# other.net
KiCad netlist of a schematic drawn in Altium Designer
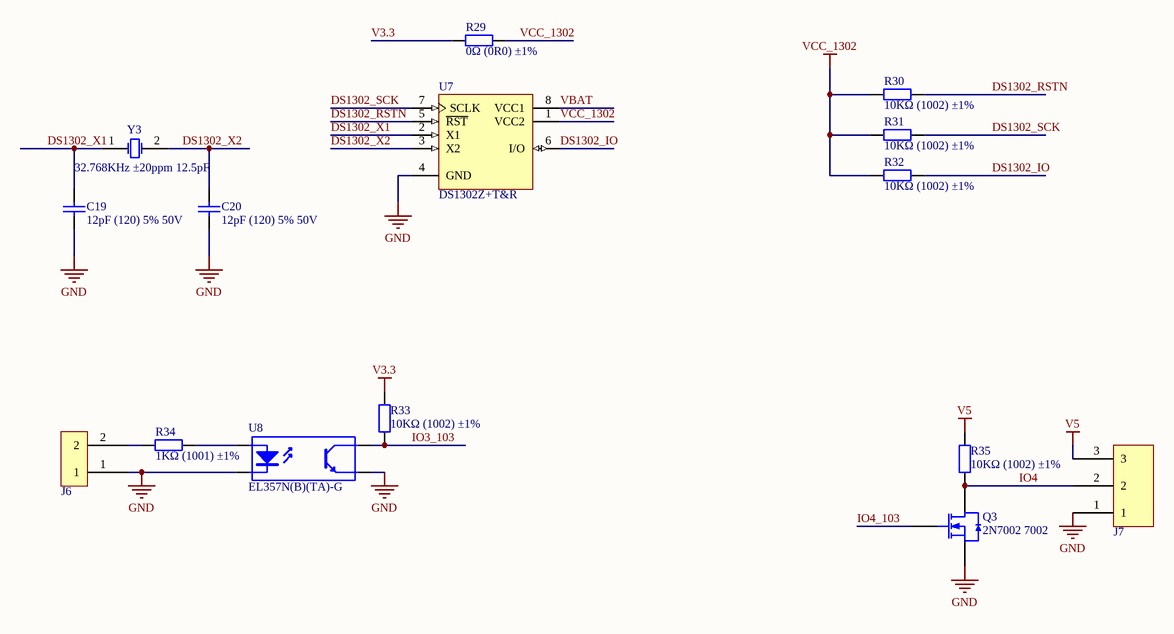
[diagram p0: other.SchDoc]

(export (version "E")
  (design (tool "Eeschema 10.0.6"))
  (components
    (comp (ref "C19")
      (value "12pF (120) 5% 50V")
      (footprint "0603_C")
      (description "贴片电容")
      (libsource (lib "Miscellaneous Devices LC") (part "0603 12pF (120) 5% 50V"))
    )
    (comp (ref "C20")
      (value "12pF (120) 5% 50V")
      (footprint "0603_C")
      (description "贴片电容")
      (libsource (lib "Miscellaneous Devices LC") (part "0603 12pF (120) 5% 50V"))
    )
    (comp (ref "J6") (value "KF301-2P") (footprint "KF301-2P") (libsource (lib "CHK-I") (part "KF301-2P")))
    (comp (ref "J7") (value "KF301-3P") (footprint "KF301-3P") (libsource (lib "CHK-I") (part "KF301-3P")))
    (comp (ref "Q3")
      (value "2N7002 7002")
      (footprint "SOT-23(SOT-23-3)")
      (description "MOS(场效应管)")
      (libsource (lib "Miscellaneous Devices LC") (part "2N7002 7002"))
    )
    (comp (ref "R29")
      (value "0Ω (0R0) ±1%")
      (footprint "1206_R")
      (description "贴片电阻")
      (libsource (lib "Miscellaneous Devices LC") (part "1206 0Ω (0R0) 1%"))
    )
    (comp (ref "R30")
      (value "10KΩ (1002) ±1%")
      (footprint "0603_R")
      (description "贴片电阻")
      (libsource (lib "Miscellaneous Devices LC") (part "0603 10KΩ (1002) 1%"))
    )
    (comp (ref "R31")
      (value "10KΩ (1002) ±1%")
      (footprint "0603_R")
      (description "贴片电阻")
      (libsource (lib "Miscellaneous Devices LC") (part "0603 10KΩ (1002) 1%"))
    )
    (comp (ref "R32")
      (value "10KΩ (1002) ±1%")
      (footprint "0603_R")
      (description "贴片电阻")
      (libsource (lib "Miscellaneous Devices LC") (part "0603 10KΩ (1002) 1%"))
    )
    (comp (ref "R33")
      (value "10KΩ (1002) ±1%")
      (footprint "1206_R")
      (description "贴片电阻")
      (libsource (lib "Miscellaneous Devices LC") (part "1206 10KΩ (1002) 1%"))
    )
    (comp (ref "R34")
      (value "1KΩ (1001) ±1%")
      (footprint "1206_R")
      (description "贴片电阻")
      (libsource (lib "Miscellaneous Devices LC") (part "1206 1KΩ (1001) 1%"))
    )
    (comp (ref "R35")
      (value "10KΩ (1002) ±1%")
      (footprint "1206_R")
      (description "贴片电阻")
      (libsource (lib "Miscellaneous Devices LC") (part "1206 10KΩ (1002) 1%"))
    )
    (comp (ref "U7")
      (value "DS1302Z+T&R")
      (footprint "SOIC-8_150mil")
      (description "实时时钟")
      (libsource (lib "Miscellaneous Devices LC") (part "DS1302Z+T&R_[C8959]"))
    )
    (comp (ref "U8")
      (value "EL357N(B)(TA)-G")
      (footprint "SOP-4_P2.54")
      (description "贴片光耦")
      (libsource (lib "Miscellaneous Devices LC") (part "EL357N(B)(TA)-G_[C6649]"))
    )
    (comp (ref "Y3")
      (value "32.768KHz ±20ppm 12.5pF")
      (footprint "SMD-3215_2P FC - 135")
      (description "贴片晶振")
      (libsource (lib "Miscellaneous Devices LC") (part "SMD-3215_2P 32.768KHz 20ppm 12.5pF"))
    )
  )
  (nets
    (net (code "1") (name "/DS1302_IO") (class "Default")
      (node (ref "R32") (pin "2") (pinfunction "2_2") (pintype "passive"))
      (node (ref "U7") (pin "6") (pinfunction "I/O_6") (pintype "bidirectional"))
    )
    (net (code "2") (name "/DS1302_RSTN") (class "Default")
      (node (ref "R30") (pin "2") (pinfunction "2_2") (pintype "passive"))
      (node (ref "U7") (pin "5") (pinfunction "~{RST}_5") (pintype "input"))
    )
    (net (code "3") (name "/DS1302_SCK") (class "Default")
      (node (ref "R31") (pin "2") (pinfunction "2_2") (pintype "passive"))
      (node (ref "U7") (pin "7") (pinfunction "SCLK_7") (pintype "input"))
    )
    (net (code "4") (name "/DS1302_X1") (class "Default")
      (node (ref "C19") (pin "2") (pinfunction "2_2") (pintype "passive"))
      (node (ref "U7") (pin "2") (pinfunction "X1_2") (pintype "input"))
      (node (ref "Y3") (pin "1") (pinfunction "OSC1_1") (pintype "passive"))
    )
    (net (code "5") (name "/DS1302_X2") (class "Default")
      (node (ref "C20") (pin "2") (pinfunction "2_2") (pintype "passive"))
      (node (ref "U7") (pin "3") (pinfunction "X2_3") (pintype "input"))
      (node (ref "Y3") (pin "2") (pinfunction "OSC2_2") (pintype "passive"))
    )
    (net (code "6") (name "/IO3_103") (class "Default")
      (node (ref "R33") (pin "1") (pinfunction "1_1") (pintype "passive"))
      (node (ref "U8") (pin "4") (pinfunction "C_4") (pintype "passive"))
    )
    (net (code "7") (name "/IO4") (class "Default")
      (node (ref "J7") (pin "2") (pinfunction "2_2") (pintype "passive"))
      (node (ref "Q3") (pin "3") (pinfunction "D_3") (pintype "passive"))
      (node (ref "R35") (pin "1") (pinfunction "1_1") (pintype "passive"))
    )
    (net (code "8") (name "/IO4_103") (class "Default")
      (node (ref "Q3") (pin "1") (pinfunction "G_1") (pintype "passive"))
    )
    (net (code "9") (name "/VBAT") (class "Default")
      (node (ref "U7") (pin "8") (pinfunction "VCC1_8") (pintype "power_in"))
    )
    (net (code "10") (name "GND") (class "Default")
      (node (ref "C19") (pin "1") (pinfunction "1_1") (pintype "passive"))
      (node (ref "C20") (pin "1") (pinfunction "1_1") (pintype "passive"))
      (node (ref "J6") (pin "1") (pinfunction "1_1") (pintype "passive"))
      (node (ref "J7") (pin "1") (pinfunction "1_1") (pintype "passive"))
      (node (ref "Q3") (pin "2") (pinfunction "S_2") (pintype "passive"))
      (node (ref "U7") (pin "4") (pinfunction "GND_4") (pintype "power_in"))
      (node (ref "U8") (pin "2") (pinfunction "K_2") (pintype "passive"))
      (node (ref "U8") (pin "3") (pinfunction "E_3") (pintype "passive"))
    )
    (net (code "11") (name "Net-(J6-Pad2)") (class "Default")
      (node (ref "J6") (pin "2") (pinfunction "2_2") (pintype "passive"))
      (node (ref "R34") (pin "1") (pinfunction "1_1") (pintype "passive"))
    )
    (net (code "12") (name "Net-(U8-A)") (class "Default")
      (node (ref "R34") (pin "2") (pinfunction "2_2") (pintype "passive"))
      (node (ref "U8") (pin "1") (pinfunction "A_1") (pintype "passive"))
    )
    (net (code "13") (name "V3.3") (class "Default")
      (node (ref "R29") (pin "1") (pinfunction "1_1") (pintype "passive"))
      (node (ref "R33") (pin "2") (pinfunction "2_2") (pintype "passive"))
    )
    (net (code "14") (name "V5") (class "Default")
      (node (ref "J7") (pin "3") (pinfunction "3_3") (pintype "passive"))
      (node (ref "R35") (pin "2") (pinfunction "2_2") (pintype "passive"))
    )
    (net (code "15") (name "VCC_1302") (class "Default")
      (node (ref "R29") (pin "2") (pinfunction "2_2") (pintype "passive"))
      (node (ref "R30") (pin "1") (pinfunction "1_1") (pintype "passive"))
      (node (ref "R31") (pin "1") (pinfunction "1_1") (pintype "passive"))
      (node (ref "R32") (pin "1") (pinfunction "1_1") (pintype "passive"))
      (node (ref "U7") (pin "1") (pinfunction "VCC2_1") (pintype "power_in"))
    )
  )
)
